# me433_1.net
KiCad netlist of a schematic drawn in EAGLE
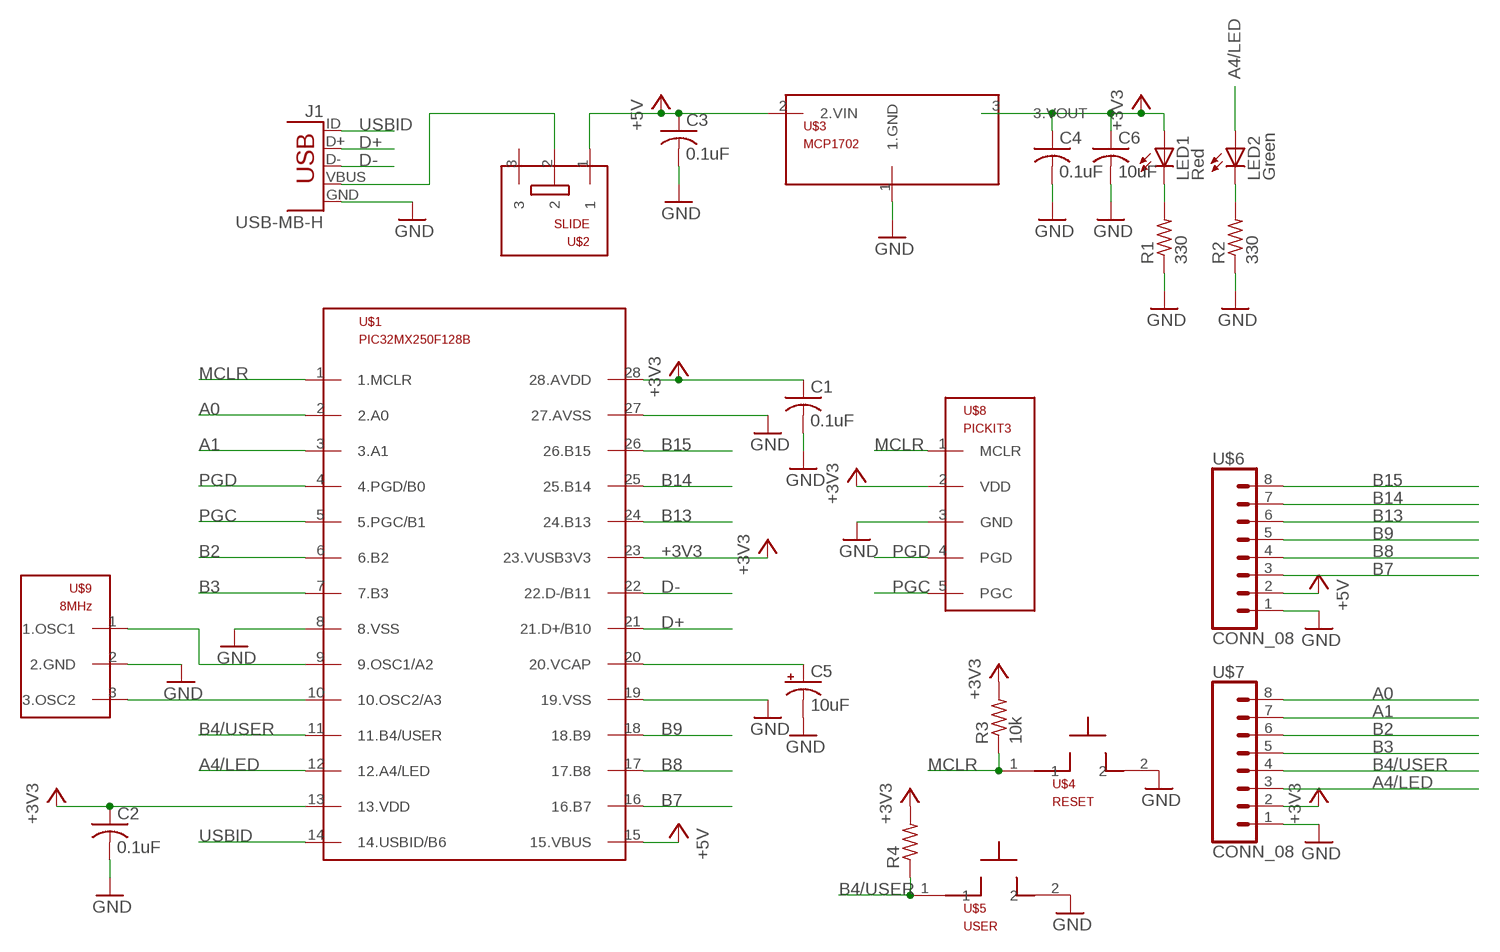
[diagram p0: schematic, sheet 1]

(export (version "E")
  (design (tool "Eeschema 10.0.6"))
  (components
    (comp (ref "C1")
      (value "0.1uF")
      (footprint "eagle-import:C025-025X050")
      (libsource (lib "eagle-import") (part "C-US025-025X050"))
    )
    (comp (ref "C2")
      (value "0.1uF")
      (footprint "eagle-import:C025-025X050")
      (libsource (lib "eagle-import") (part "C-US025-025X050"))
    )
    (comp (ref "C3")
      (value "0.1uF")
      (footprint "eagle-import:C025-025X050")
      (libsource (lib "eagle-import") (part "C-US025-025X050"))
    )
    (comp (ref "C4")
      (value "0.1uF")
      (footprint "eagle-import:C025-025X050")
      (libsource (lib "eagle-import") (part "C-US025-025X050"))
    )
    (comp (ref "C5")
      (value "10uF")
      (footprint "eagle-import:B45181B")
      (libsource (lib "eagle-import") (part "CPOL-USB45181B"))
    )
    (comp (ref "C6")
      (value "10uF")
      (footprint "eagle-import:C025-025X050")
      (libsource (lib "eagle-import") (part "C-US025-025X050"))
    )
    (comp (ref "J1")
      (value "USB-MB-H")
      (footprint "eagle-import:USB-MB-H")
      (libsource (lib "eagle-import") (part "USB-MB-H"))
    )
    (comp (ref "LED1")
      (value "Red")
      (footprint "eagle-import:LED3MM")
      (libsource (lib "eagle-import") (part "LED3MM"))
    )
    (comp (ref "LED2")
      (value "Green")
      (footprint "eagle-import:LED3MM")
      (libsource (lib "eagle-import") (part "LED3MM"))
    )
    (comp (ref "R1")
      (value "330")
      (footprint "eagle-import:0207_10")
      (libsource (lib "eagle-import") (part "resistor_348_R-US_0207/10"))
    )
    (comp (ref "R2")
      (value "330")
      (footprint "eagle-import:0207_10")
      (libsource (lib "eagle-import") (part "resistor_348_R-US_0207/10"))
    )
    (comp (ref "R3")
      (value "10k")
      (footprint "eagle-import:0207_10")
      (libsource (lib "eagle-import") (part "R-US_0207/10"))
    )
    (comp (ref "R4")
      (value "R-US_0207/10")
      (footprint "eagle-import:0207_10")
      (libsource (lib "eagle-import") (part "R-US_0207/10"))
    )
    (comp (ref "U$1")
      (value "PIC32MX250F128B")
      (footprint "eagle-import:DIL28-3")
      (libsource (lib "eagle-import") (part "PIC32MX250F128B"))
    )
    (comp (ref "U$2")
      (value "SLIDE")
      (footprint "eagle-import:SLIDE")
      (libsource (lib "eagle-import") (part "SLIDE"))
    )
    (comp (ref "U$3")
      (value "MCP1702")
      (footprint "eagle-import:TO92")
      (libsource (lib "eagle-import") (part "MCP1702"))
    )
    (comp (ref "U$4")
      (value "RESET")
      (footprint "eagle-import:PB")
      (libsource (lib "eagle-import") (part "PB"))
    )
    (comp (ref "U$5")
      (value "USER")
      (footprint "eagle-import:PB")
      (libsource (lib "eagle-import") (part "PB"))
    )
    (comp (ref "U$6")
      (value "CONN_08")
      (footprint "eagle-import:1X08")
      (libsource (lib "eagle-import") (part "CONN_08"))
    )
    (comp (ref "U$7")
      (value "CONN_08")
      (footprint "eagle-import:1X08")
      (libsource (lib "eagle-import") (part "CONN_08"))
    )
    (comp (ref "U$8")
      (value "PICKIT3")
      (footprint "eagle-import:1X05")
      (libsource (lib "eagle-import") (part "PICKIT3"))
    )
    (comp (ref "U$9")
      (value "8MHz")
      (footprint "eagle-import:OSC")
      (libsource (lib "eagle-import") (part "OSC"))
    )
  )
  (nets
    (net (code "1") (name "+3V3") (class "Default")
      (node (ref "C1") (pin "1") (pinfunction "1_1") (pintype "passive"))
      (node (ref "C2") (pin "1") (pinfunction "1_1") (pintype "passive"))
      (node (ref "C4") (pin "1") (pinfunction "1_1") (pintype "passive"))
      (node (ref "C6") (pin "1") (pinfunction "1_1") (pintype "passive"))
      (node (ref "LED1") (pin "A") (pinfunction "A_A") (pintype "passive"))
      (node (ref "R3") (pin "2") (pinfunction "2_2") (pintype "passive"))
      (node (ref "R4") (pin "2") (pinfunction "2_2") (pintype "passive"))
      (node (ref "U$1") (pin "13") (pinfunction "13.VDD_13") (pintype "bidirectional"))
      (node (ref "U$1") (pin "23") (pinfunction "23.VUSB3V3_23") (pintype "bidirectional"))
      (node (ref "U$1") (pin "28") (pinfunction "28.AVDD_28") (pintype "bidirectional"))
      (node (ref "U$3") (pin "3") (pinfunction "3.VOUT_3") (pintype "bidirectional"))
      (node (ref "U$7") (pin "2") (pinfunction "2_2") (pintype "passive"))
      (node (ref "U$8") (pin "2") (pinfunction "VDD_2") (pintype "bidirectional"))
    )
    (net (code "2") (name "+5V") (class "Default")
      (node (ref "C3") (pin "1") (pinfunction "1_1") (pintype "passive"))
      (node (ref "U$1") (pin "15") (pinfunction "15.VBUS_15") (pintype "bidirectional"))
      (node (ref "U$2") (pin "1") (pinfunction "1_1") (pintype "bidirectional"))
      (node (ref "U$3") (pin "2") (pinfunction "2.VIN_2") (pintype "bidirectional"))
      (node (ref "U$6") (pin "2") (pinfunction "2_2") (pintype "passive"))
    )
    (net (code "3") (name "/A0") (class "Default")
      (node (ref "U$1") (pin "2") (pinfunction "2.A0_2") (pintype "bidirectional"))
      (node (ref "U$7") (pin "8") (pinfunction "8_8") (pintype "passive"))
    )
    (net (code "4") (name "/A1") (class "Default")
      (node (ref "U$1") (pin "3") (pinfunction "3.A1_3") (pintype "bidirectional"))
      (node (ref "U$7") (pin "7") (pinfunction "7_7") (pintype "passive"))
    )
    (net (code "5") (name "/A4{slash}LED") (class "Default")
      (node (ref "LED2") (pin "A") (pinfunction "A_A") (pintype "passive"))
      (node (ref "U$1") (pin "12") (pinfunction "12.A4/LED_12") (pintype "bidirectional"))
      (node (ref "U$7") (pin "3") (pinfunction "3_3") (pintype "passive"))
    )
    (net (code "6") (name "/B2") (class "Default")
      (node (ref "U$1") (pin "6") (pinfunction "6.B2_6") (pintype "bidirectional"))
      (node (ref "U$7") (pin "6") (pinfunction "6_6") (pintype "passive"))
    )
    (net (code "7") (name "/B3") (class "Default")
      (node (ref "U$1") (pin "7") (pinfunction "7.B3_7") (pintype "bidirectional"))
      (node (ref "U$7") (pin "5") (pinfunction "5_5") (pintype "passive"))
    )
    (net (code "8") (name "/B4{slash}USER") (class "Default")
      (node (ref "R4") (pin "1") (pinfunction "1_1") (pintype "passive"))
      (node (ref "U$1") (pin "11") (pinfunction "11.B4/USER_11") (pintype "bidirectional"))
      (node (ref "U$5") (pin "1") (pinfunction "1_1") (pintype "bidirectional"))
      (node (ref "U$7") (pin "4") (pinfunction "4_4") (pintype "passive"))
    )
    (net (code "9") (name "/B7") (class "Default")
      (node (ref "U$1") (pin "16") (pinfunction "16.B7_16") (pintype "bidirectional"))
      (node (ref "U$6") (pin "3") (pinfunction "3_3") (pintype "passive"))
    )
    (net (code "10") (name "/B8") (class "Default")
      (node (ref "U$1") (pin "17") (pinfunction "17.B8_17") (pintype "bidirectional"))
      (node (ref "U$6") (pin "4") (pinfunction "4_4") (pintype "passive"))
    )
    (net (code "11") (name "/B9") (class "Default")
      (node (ref "U$1") (pin "18") (pinfunction "18.B9_18") (pintype "bidirectional"))
      (node (ref "U$6") (pin "5") (pinfunction "5_5") (pintype "passive"))
    )
    (net (code "12") (name "/B13") (class "Default")
      (node (ref "U$1") (pin "24") (pinfunction "24.B13_24") (pintype "bidirectional"))
      (node (ref "U$6") (pin "6") (pinfunction "6_6") (pintype "passive"))
    )
    (net (code "13") (name "/B14") (class "Default")
      (node (ref "U$1") (pin "25") (pinfunction "25.B14_25") (pintype "bidirectional"))
      (node (ref "U$6") (pin "7") (pinfunction "7_7") (pintype "passive"))
    )
    (net (code "14") (name "/B15") (class "Default")
      (node (ref "U$1") (pin "26") (pinfunction "26.B15_26") (pintype "bidirectional"))
      (node (ref "U$6") (pin "8") (pinfunction "8_8") (pintype "passive"))
    )
    (net (code "15") (name "/D+") (class "Default")
      (node (ref "J1") (pin "D+") (pinfunction "D+_D+") (pintype "bidirectional"))
      (node (ref "U$1") (pin "21") (pinfunction "21.D+/B10_21") (pintype "bidirectional"))
    )
    (net (code "16") (name "/D-") (class "Default")
      (node (ref "J1") (pin "D-") (pinfunction "D-_D-") (pintype "bidirectional"))
      (node (ref "U$1") (pin "22") (pinfunction "22.D-/B11_22") (pintype "bidirectional"))
    )
    (net (code "17") (name "/MCLR") (class "Default")
      (node (ref "R3") (pin "1") (pinfunction "1_1") (pintype "passive"))
      (node (ref "U$1") (pin "1") (pinfunction "1.MCLR_1") (pintype "bidirectional"))
      (node (ref "U$4") (pin "1") (pinfunction "1_1") (pintype "bidirectional"))
      (node (ref "U$8") (pin "1") (pinfunction "MCLR_1") (pintype "bidirectional"))
    )
    (net (code "18") (name "/PGC") (class "Default")
      (node (ref "U$1") (pin "5") (pinfunction "5.PGC/B1_5") (pintype "bidirectional"))
      (node (ref "U$8") (pin "5") (pinfunction "PGC_5") (pintype "bidirectional"))
    )
    (net (code "19") (name "/PGD") (class "Default")
      (node (ref "U$1") (pin "4") (pinfunction "4.PGD/B0_4") (pintype "bidirectional"))
      (node (ref "U$8") (pin "4") (pinfunction "PGD_4") (pintype "bidirectional"))
    )
    (net (code "20") (name "/USBID") (class "Default")
      (node (ref "J1") (pin "ID") (pinfunction "ID_ID") (pintype "bidirectional"))
      (node (ref "U$1") (pin "14") (pinfunction "14.USBID/B6_14") (pintype "bidirectional"))
    )
    (net (code "21") (name "GND") (class "Default")
      (node (ref "C1") (pin "2") (pinfunction "2_2") (pintype "passive"))
      (node (ref "C2") (pin "2") (pinfunction "2_2") (pintype "passive"))
      (node (ref "C3") (pin "2") (pinfunction "2_2") (pintype "passive"))
      (node (ref "C4") (pin "2") (pinfunction "2_2") (pintype "passive"))
      (node (ref "C5") (pin "-") (pinfunction "-_-") (pintype "passive"))
      (node (ref "C6") (pin "2") (pinfunction "2_2") (pintype "passive"))
      (node (ref "J1") (pin "GND") (pinfunction "GND_GND") (pintype "bidirectional"))
      (node (ref "R1") (pin "1") (pinfunction "1_1") (pintype "passive"))
      (node (ref "R2") (pin "1") (pinfunction "1_1") (pintype "passive"))
      (node (ref "U$1") (pin "19") (pinfunction "19.VSS_19") (pintype "bidirectional"))
      (node (ref "U$1") (pin "27") (pinfunction "27.AVSS_27") (pintype "bidirectional"))
      (node (ref "U$1") (pin "8") (pinfunction "8.VSS_8") (pintype "bidirectional"))
      (node (ref "U$3") (pin "1") (pinfunction "1.GND_1") (pintype "bidirectional"))
      (node (ref "U$4") (pin "2") (pinfunction "2_2") (pintype "bidirectional"))
      (node (ref "U$5") (pin "2") (pinfunction "2_2") (pintype "bidirectional"))
      (node (ref "U$6") (pin "1") (pinfunction "1_1") (pintype "passive"))
      (node (ref "U$7") (pin "1") (pinfunction "1_1") (pintype "passive"))
      (node (ref "U$8") (pin "3") (pinfunction "GND_3") (pintype "bidirectional"))
      (node (ref "U$9") (pin "2") (pinfunction "2.GND_2") (pintype "bidirectional"))
    )
    (net (code "22") (name "Net-(J1-PadVBUS)") (class "Default")
      (node (ref "J1") (pin "VBUS") (pinfunction "VBUS_VBUS") (pintype "bidirectional"))
      (node (ref "U$2") (pin "2") (pinfunction "2_2") (pintype "bidirectional"))
    )
    (net (code "23") (name "Net-(LED1-C)") (class "Default")
      (node (ref "LED1") (pin "K") (pinfunction "C_K") (pintype "passive"))
      (node (ref "R1") (pin "2") (pinfunction "2_2") (pintype "passive"))
    )
    (net (code "24") (name "Net-(LED2-C)") (class "Default")
      (node (ref "LED2") (pin "K") (pinfunction "C_K") (pintype "passive"))
      (node (ref "R2") (pin "2") (pinfunction "2_2") (pintype "passive"))
    )
    (net (code "25") (name "Net-(U$1-9.OSC1{slash}A2)") (class "Default")
      (node (ref "U$1") (pin "9") (pinfunction "9.OSC1/A2_9") (pintype "bidirectional"))
      (node (ref "U$9") (pin "1") (pinfunction "1.OSC1_1") (pintype "bidirectional"))
    )
    (net (code "26") (name "Net-(U$1-10.OSC2{slash}A3)") (class "Default")
      (node (ref "U$1") (pin "10") (pinfunction "10.OSC2/A3_10") (pintype "bidirectional"))
      (node (ref "U$9") (pin "3") (pinfunction "3.OSC2_3") (pintype "bidirectional"))
    )
    (net (code "27") (name "Net-(U$1-20.VCAP)") (class "Default")
      (node (ref "C5") (pin "+") (pinfunction "+_+") (pintype "passive"))
      (node (ref "U$1") (pin "20") (pinfunction "20.VCAP_20") (pintype "bidirectional"))
    )
    (net (code "28") (name "unconnected-(U$2-Pad3)") (class "Default")
      (node (ref "U$2") (pin "3") (pinfunction "3_3") (pintype "bidirectional"))
    )
  )
)
